# schematic.net
KiCad netlist of a schematic drawn in EasyEDA
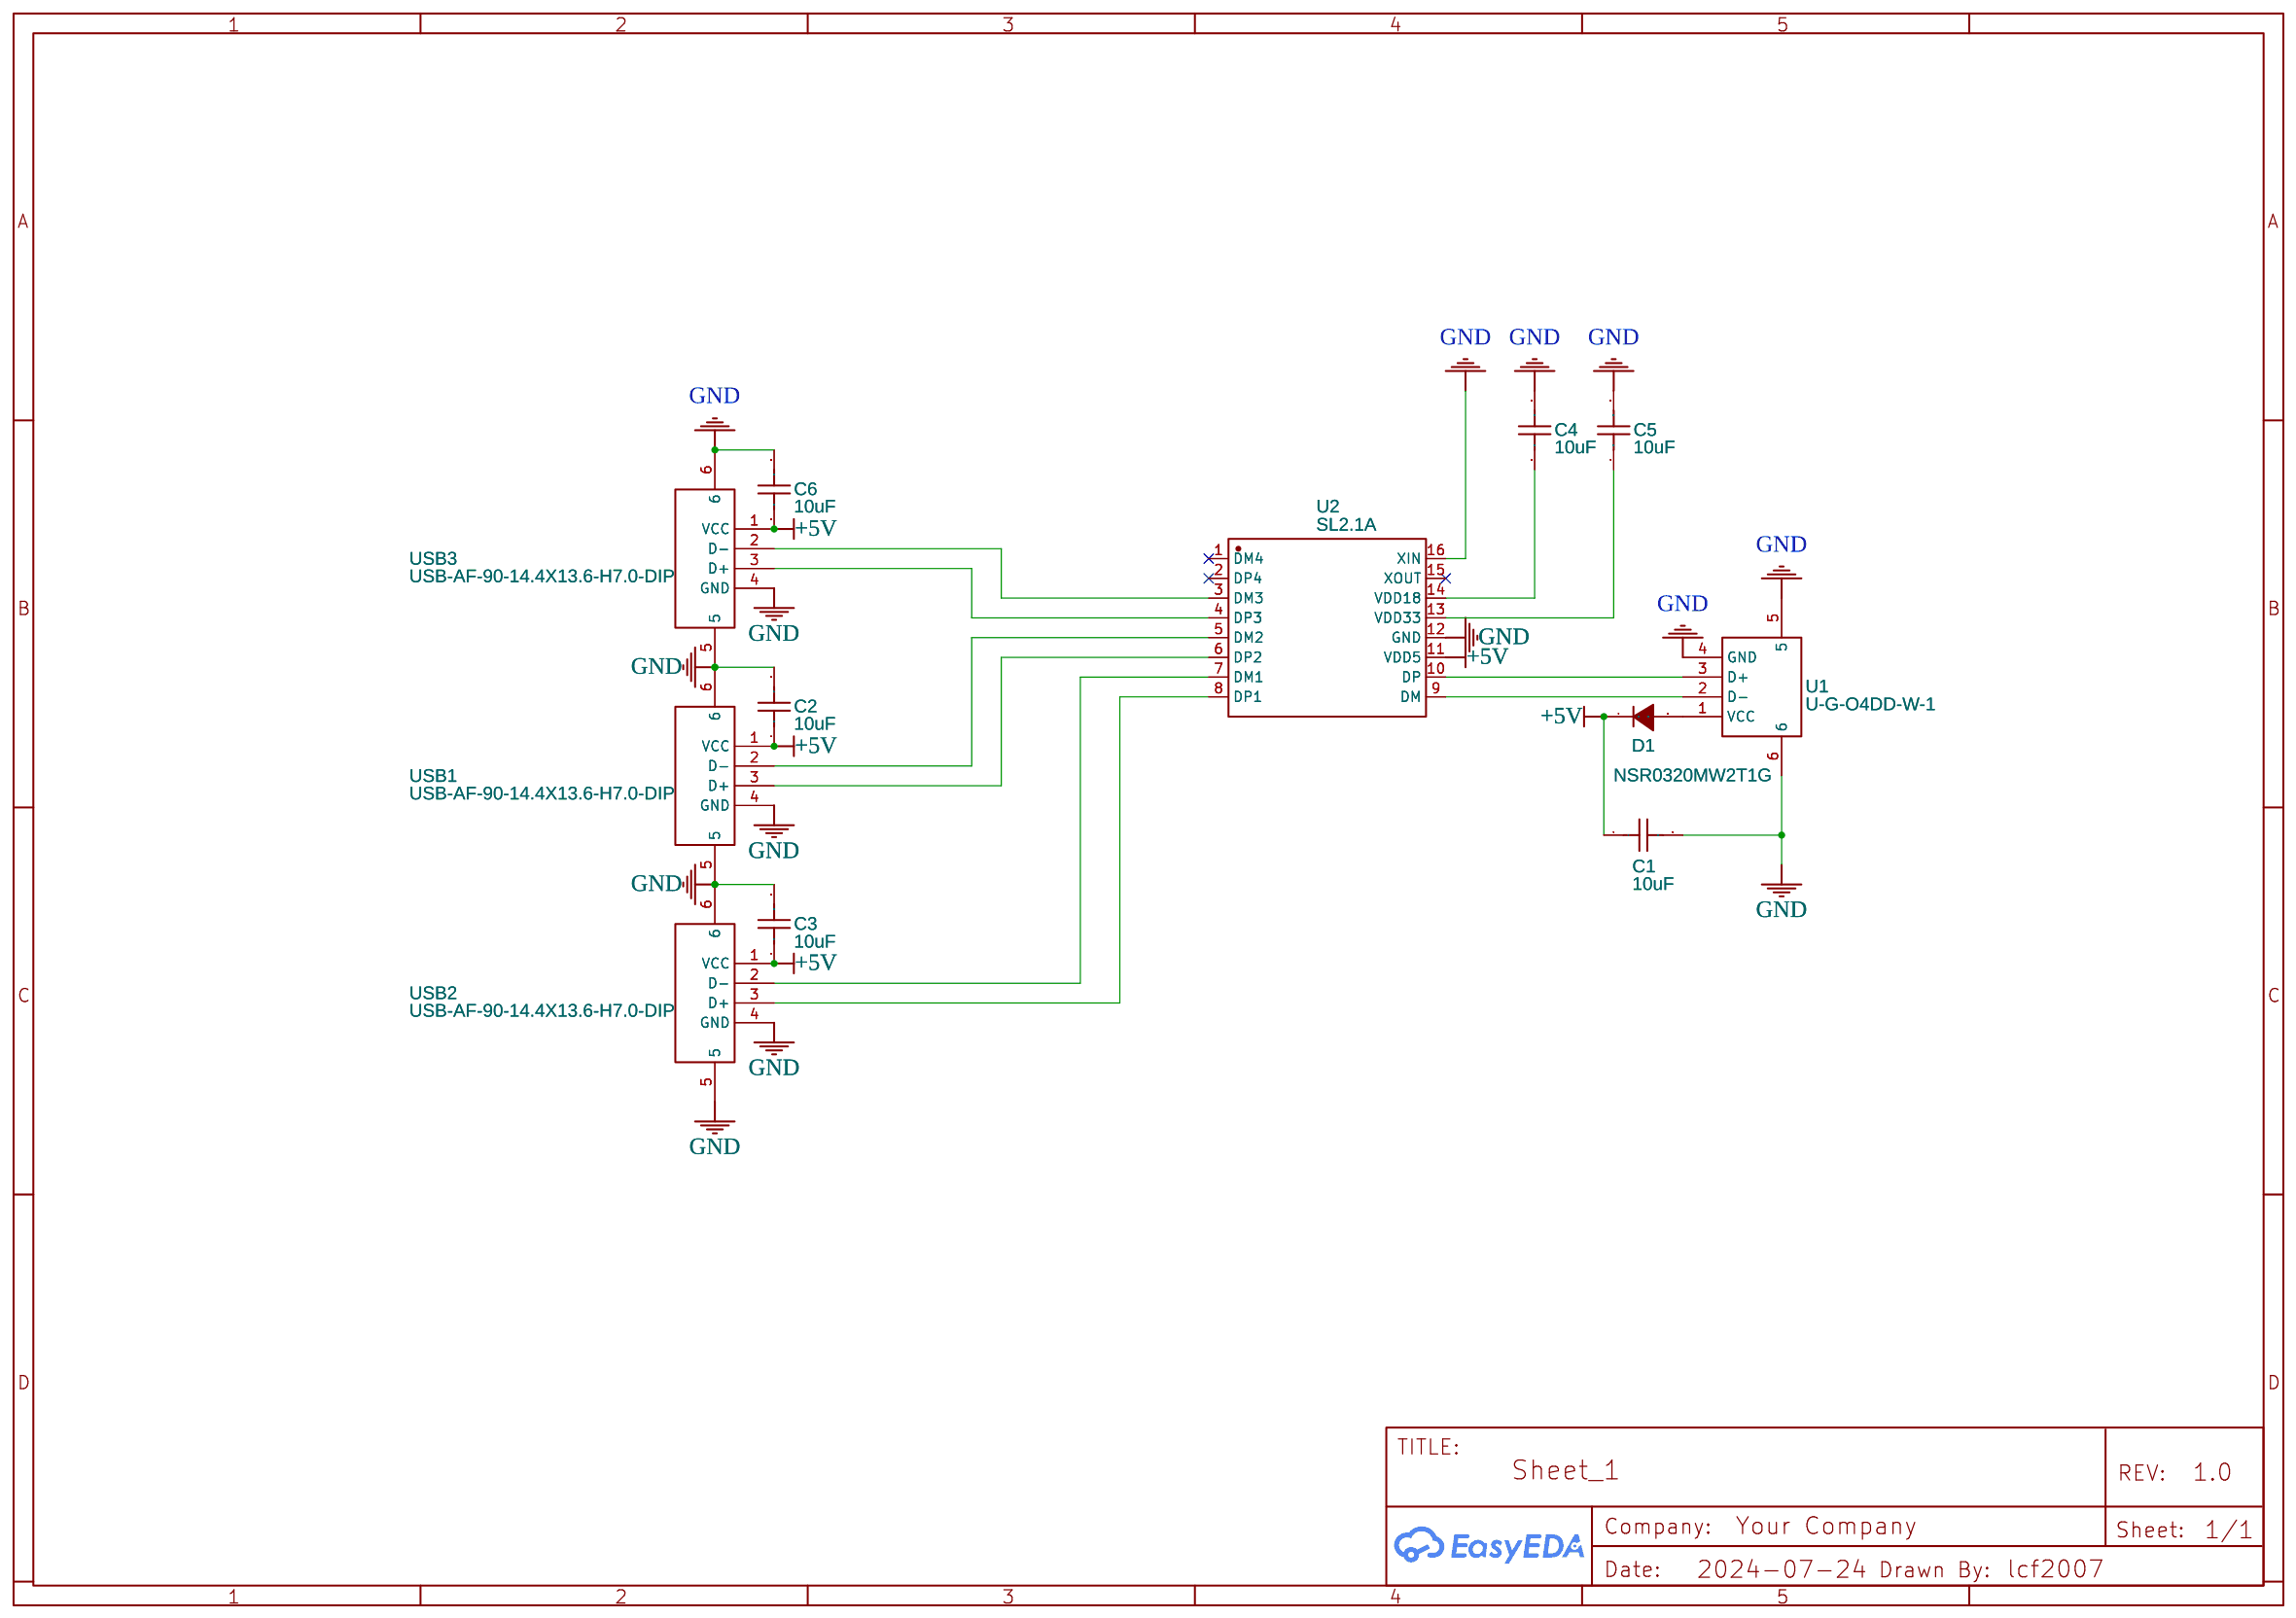
[diagram p0: schematic sheet]

(export (version "E")
  (design (tool "Eeschema 10.0.6"))
  (components
    (comp (ref "C1")
      (value "10uF")
      (fields
        (field (name "Manufacturer Part") "CL10A106KP8NNNC")
        (field (name "Manufacturer") "SAMSUNG(三星)")
      )
      (libsource (lib "") (part "CL10A106KP8NNNC_1"))
    )
    (comp (ref "C2")
      (value "10uF")
      (fields
        (field (name "Manufacturer Part") "CL10A106KP8NNNC")
        (field (name "Manufacturer") "SAMSUNG(三星)")
      )
      (libsource (lib "") (part "CL10A106KP8NNNC"))
    )
    (comp (ref "C3")
      (value "10uF")
      (fields
        (field (name "Manufacturer Part") "CL10A106KP8NNNC")
        (field (name "Manufacturer") "SAMSUNG(三星)")
      )
      (libsource (lib "") (part "CL10A106KP8NNNC"))
    )
    (comp (ref "C4")
      (value "10uF")
      (fields
        (field (name "Manufacturer Part") "CL10A106KP8NNNC")
        (field (name "Manufacturer") "SAMSUNG(三星)")
      )
      (libsource (lib "") (part "CL10A106KP8NNNC"))
    )
    (comp (ref "C5")
      (value "10uF")
      (fields
        (field (name "Manufacturer Part") "CL10A106KP8NNNC")
        (field (name "Manufacturer") "SAMSUNG(三星)")
      )
      (libsource (lib "") (part "CL10A106KP8NNNC"))
    )
    (comp (ref "C6")
      (value "10uF")
      (fields
        (field (name "Manufacturer Part") "CL10A106KP8NNNC")
        (field (name "Manufacturer") "SAMSUNG(三星)")
      )
      (libsource (lib "") (part "CL10A106KP8NNNC"))
    )
    (comp (ref "D1")
      (value "NSR0320MW2T1G")
      (fields (field (name "Manufacturer") "onsemi(安森美)"))
      (libsource (lib "") (part "NSR0320MW2T1G"))
    )
    (comp (ref "U1")
      (value "U-G-O4DD-W-1")
      (fields (field (name "Manufacturer") "韩国韩荣"))
      (libsource (lib "") (part "U-G-O4DD-W-1"))
    )
    (comp (ref "U2")
      (value "SL2.1A")
      (fields (field (name "Manufacturer") "CoreChips(和芯润德)"))
      (libsource (lib "") (part "SL2.1A"))
    )
    (comp (ref "USB1")
      (value "USB-AF-90-14.4X13.6-H7.0-DIP")
      (fields (field (name "Manufacturer Part") "903-131A1011D10100") (field (name "Manufacturer") "精拓金"))
      (libsource (lib "") (part "USB-AF-90-14.4X13.6-H7.0-DIP"))
    )
    (comp (ref "USB2")
      (value "USB-AF-90-14.4X13.6-H7.0-DIP")
      (fields (field (name "Manufacturer Part") "903-131A1011D10100") (field (name "Manufacturer") "精拓金"))
      (libsource (lib "") (part "USB-AF-90-14.4X13.6-H7.0-DIP"))
    )
    (comp (ref "USB3")
      (value "USB-AF-90-14.4X13.6-H7.0-DIP")
      (fields (field (name "Manufacturer Part") "903-131A1011D10100") (field (name "Manufacturer") "精拓金"))
      (libsource (lib "") (part "USB-AF-90-14.4X13.6-H7.0-DIP"))
    )
  )
  (nets
    (net (code "1") (name "+5V") (class "Default")
      (node (ref "C1") (pin "1") (pinfunction "1_1") (pintype "unspecified"))
      (node (ref "C2") (pin "1") (pinfunction "1_1") (pintype "unspecified"))
      (node (ref "C3") (pin "1") (pinfunction "1_1") (pintype "unspecified"))
      (node (ref "C6") (pin "1") (pinfunction "1_1") (pintype "unspecified"))
      (node (ref "D1") (pin "1") (pinfunction "C_1") (pintype "unspecified"))
      (node (ref "U2") (pin "11") (pinfunction "VDD5_11") (pintype "unspecified"))
      (node (ref "USB1") (pin "1") (pinfunction "VCC_1") (pintype "unspecified"))
      (node (ref "USB2") (pin "1") (pinfunction "VCC_1") (pintype "unspecified"))
      (node (ref "USB3") (pin "1") (pinfunction "VCC_1") (pintype "unspecified"))
    )
    (net (code "2") (name "GND") (class "Default")
      (node (ref "C1") (pin "2") (pinfunction "2_2") (pintype "unspecified"))
      (node (ref "C2") (pin "2") (pinfunction "2_2") (pintype "unspecified"))
      (node (ref "C3") (pin "2") (pinfunction "2_2") (pintype "unspecified"))
      (node (ref "C4") (pin "2") (pinfunction "2_2") (pintype "unspecified"))
      (node (ref "C5") (pin "2") (pinfunction "2_2") (pintype "unspecified"))
      (node (ref "C6") (pin "2") (pinfunction "2_2") (pintype "unspecified"))
      (node (ref "U1") (pin "4") (pinfunction "GND_4") (pintype "unspecified"))
      (node (ref "U1") (pin "5") (pinfunction "5_5") (pintype "unspecified"))
      (node (ref "U1") (pin "6") (pinfunction "6_6") (pintype "unspecified"))
      (node (ref "U2") (pin "12") (pinfunction "GND_12") (pintype "unspecified"))
      (node (ref "U2") (pin "16") (pinfunction "XIN_16") (pintype "unspecified"))
      (node (ref "USB1") (pin "4") (pinfunction "GND_4") (pintype "unspecified"))
      (node (ref "USB1") (pin "5") (pinfunction "5_5") (pintype "unspecified"))
      (node (ref "USB1") (pin "6") (pinfunction "6_6") (pintype "unspecified"))
      (node (ref "USB2") (pin "4") (pinfunction "GND_4") (pintype "unspecified"))
      (node (ref "USB2") (pin "5") (pinfunction "5_5") (pintype "unspecified"))
      (node (ref "USB2") (pin "6") (pinfunction "6_6") (pintype "unspecified"))
      (node (ref "USB3") (pin "4") (pinfunction "GND_4") (pintype "unspecified"))
      (node (ref "USB3") (pin "5") (pinfunction "5_5") (pintype "unspecified"))
      (node (ref "USB3") (pin "6") (pinfunction "6_6") (pintype "unspecified"))
    )
    (net (code "3") (name "Net-(D1-A)") (class "Default")
      (node (ref "D1") (pin "2") (pinfunction "A_2") (pintype "unspecified"))
      (node (ref "U1") (pin "1") (pinfunction "VCC_1") (pintype "unspecified"))
    )
    (net (code "4") (name "Net-(U1-D+)") (class "Default")
      (node (ref "U1") (pin "3") (pinfunction "D+_3") (pintype "unspecified"))
      (node (ref "U2") (pin "10") (pinfunction "DP_10") (pintype "unspecified"))
    )
    (net (code "5") (name "Net-(U1-D-)") (class "Default")
      (node (ref "U1") (pin "2") (pinfunction "D-_2") (pintype "unspecified"))
      (node (ref "U2") (pin "9") (pinfunction "DM_9") (pintype "unspecified"))
    )
    (net (code "6") (name "Net-(U2-DM1)") (class "Default")
      (node (ref "U2") (pin "7") (pinfunction "DM1_7") (pintype "unspecified"))
      (node (ref "USB2") (pin "2") (pinfunction "D-_2") (pintype "unspecified"))
    )
    (net (code "7") (name "Net-(U2-DM2)") (class "Default")
      (node (ref "U2") (pin "5") (pinfunction "DM2_5") (pintype "unspecified"))
      (node (ref "USB1") (pin "2") (pinfunction "D-_2") (pintype "unspecified"))
    )
    (net (code "8") (name "Net-(U2-DM3)") (class "Default")
      (node (ref "U2") (pin "3") (pinfunction "DM3_3") (pintype "unspecified"))
      (node (ref "USB3") (pin "2") (pinfunction "D-_2") (pintype "unspecified"))
    )
    (net (code "9") (name "Net-(U2-DP1)") (class "Default")
      (node (ref "U2") (pin "8") (pinfunction "DP1_8") (pintype "unspecified"))
      (node (ref "USB2") (pin "3") (pinfunction "D+_3") (pintype "unspecified"))
    )
    (net (code "10") (name "Net-(U2-DP2)") (class "Default")
      (node (ref "U2") (pin "6") (pinfunction "DP2_6") (pintype "unspecified"))
      (node (ref "USB1") (pin "3") (pinfunction "D+_3") (pintype "unspecified"))
    )
    (net (code "11") (name "Net-(U2-DP3)") (class "Default")
      (node (ref "U2") (pin "4") (pinfunction "DP3_4") (pintype "unspecified"))
      (node (ref "USB3") (pin "3") (pinfunction "D+_3") (pintype "unspecified"))
    )
    (net (code "12") (name "Net-(U2-VDD18)") (class "Default")
      (node (ref "C4") (pin "1") (pinfunction "1_1") (pintype "unspecified"))
      (node (ref "U2") (pin "14") (pinfunction "VDD18_14") (pintype "unspecified"))
    )
    (net (code "13") (name "Net-(U2-VDD33)") (class "Default")
      (node (ref "C5") (pin "1") (pinfunction "1_1") (pintype "unspecified"))
      (node (ref "U2") (pin "13") (pinfunction "VDD33_13") (pintype "unspecified"))
    )
    (net (code "14") (name "unconnected-(U2-DM4-Pad1)") (class "Default")
      (node (ref "U2") (pin "1") (pinfunction "DM4_1") (pintype "unspecified+no_connect"))
    )
    (net (code "15") (name "unconnected-(U2-DP4-Pad2)") (class "Default")
      (node (ref "U2") (pin "2") (pinfunction "DP4_2") (pintype "unspecified+no_connect"))
    )
    (net (code "16") (name "unconnected-(U2-XOUT-Pad15)") (class "Default")
      (node (ref "U2") (pin "15") (pinfunction "XOUT_15") (pintype "unspecified+no_connect"))
    )
  )
)
